# programmer_328.net
KiCad netlist of a schematic drawn in EAGLE
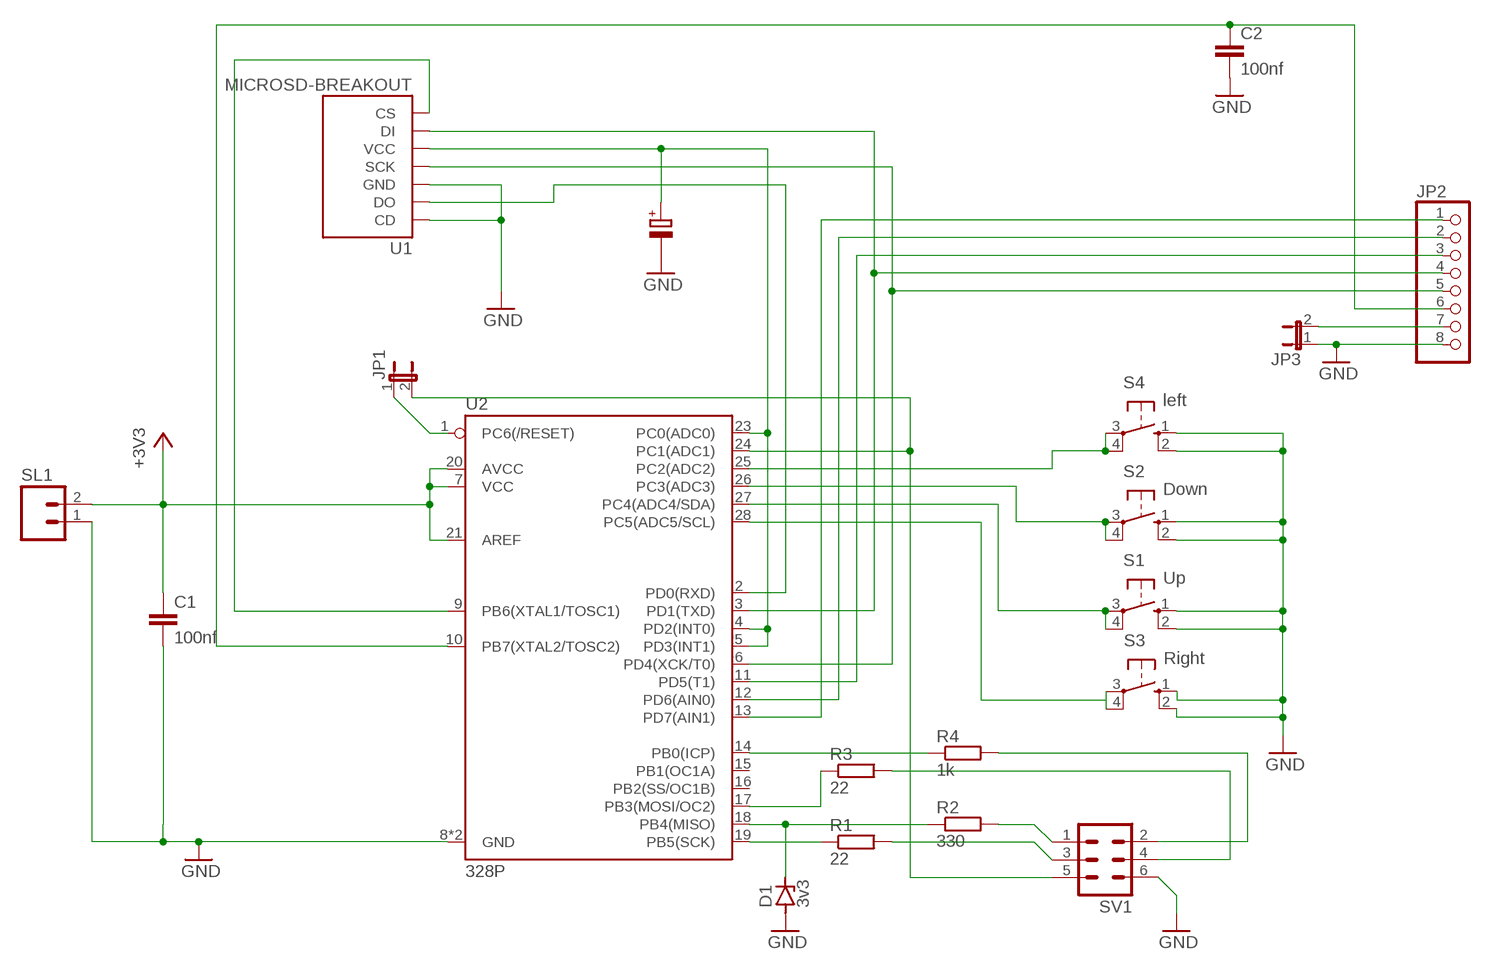
[diagram p0: schematic, sheet 1]

(export (version "E")
  (design (tool "Eeschema 10.0.6"))
  (components
    (comp (ref "C1")
      (value "100nf")
      (footprint "eagle-import:C2.5-2")
      (libsource (lib "eagle-import") (part "C2.5/2"))
    )
    (comp (ref "C2")
      (value "100nf")
      (footprint "eagle-import:C2.5-2")
      (libsource (lib "eagle-import") (part "C2.5/2"))
    )
    (comp (ref "D1")
      (value "3v3")
      (footprint "eagle-import:DO41Z10")
      (libsource (lib "eagle-import") (part "ZENER-DIODEDO41Z10"))
    )
    (comp (ref "JP1")
      (value "JP1E")
      (footprint "eagle-import:JP1")
      (libsource (lib "eagle-import") (part "JP1E"))
    )
    (comp (ref "JP2")
      (value "PINHD-1X8")
      (footprint "eagle-import:1X08")
      (libsource (lib "eagle-import") (part "PINHD-1X8"))
    )
    (comp (ref "JP3")
      (value "JP1E")
      (footprint "eagle-import:JP1")
      (libsource (lib "eagle-import") (part "JP1E"))
    )
    (comp (ref "R1")
      (value "22")
      (footprint "eagle-import:0207_12")
      (libsource (lib "eagle-import") (part "R-EU_0207/12"))
    )
    (comp (ref "R2")
      (value "330")
      (footprint "eagle-import:0207_12")
      (libsource (lib "eagle-import") (part "R-EU_0207/12"))
    )
    (comp (ref "R3")
      (value "22")
      (footprint "eagle-import:0207_12")
      (libsource (lib "eagle-import") (part "R-EU_0207/12"))
    )
    (comp (ref "R4")
      (value "1k")
      (footprint "eagle-import:0207_12")
      (libsource (lib "eagle-import") (part "R-EU_0207/12"))
    )
    (comp (ref "S1")
      (value "Up")
      (footprint "eagle-import:B3F-10XX")
      (fields (field (name "MPN") "B3F-1000"))
      (libsource (lib "eagle-import") (part "10-XX"))
    )
    (comp (ref "S2")
      (value "Down")
      (footprint "eagle-import:B3F-10XX")
      (fields (field (name "MPN") "B3F-1000"))
      (libsource (lib "eagle-import") (part "10-XX"))
    )
    (comp (ref "S3")
      (value "Right")
      (footprint "eagle-import:B3F-10XX")
      (fields (field (name "MPN") "B3F-1000"))
      (libsource (lib "eagle-import") (part "10-XX"))
    )
    (comp (ref "S4")
      (value "left")
      (footprint "eagle-import:B3F-10XX")
      (fields (field (name "MPN") "B3F-1000"))
      (libsource (lib "eagle-import") (part "10-XX"))
    )
    (comp (ref "SL1")
      (value "M02")
      (footprint "eagle-import:02P")
      (libsource (lib "eagle-import") (part "M02"))
    )
    (comp (ref "SV1")
      (value "MA03-2")
      (footprint "eagle-import:MA03-2")
      (libsource (lib "eagle-import") (part "MA03-2"))
    )
    (comp (ref "U1")
      (value "MICROSD-BREAKOUT")
      (footprint "eagle-import:MICROSD-BREAKOUT")
      (libsource (lib "eagle-import") (part "MICROSD-BREAKOUT"))
    )
    (comp (ref "U2")
      (value "328P")
      (footprint "eagle-import:DIP28")
      (libsource (lib "eagle-import") (part "ATMEGA328P_PDIP"))
    )
  )
  (nets
    (net (code "1") (name "+3V3") (class "Default")
      (node (ref "C1") (pin "1") (pinfunction "1_1") (pintype "passive"))
      (node (ref "SL1") (pin "2") (pinfunction "2_2") (pintype "passive"))
      (node (ref "U2") (pin "20") (pinfunction "AVCC_20") (pintype "bidirectional"))
      (node (ref "U2") (pin "21") (pinfunction "AREF_21") (pintype "bidirectional"))
      (node (ref "U2") (pin "7") (pinfunction "VCC_7") (pintype "bidirectional"))
    )
    (net (code "2") (name "GND") (class "Default")
      (node (ref "C1") (pin "2") (pinfunction "2_2") (pintype "passive"))
      (node (ref "C2") (pin "2") (pinfunction "2_2") (pintype "passive"))
      (node (ref "D1") (pin "A") (pinfunction "A_A") (pintype "passive"))
      (node (ref "JP2") (pin "8") (pinfunction "8_8") (pintype "passive"))
      (node (ref "JP3") (pin "1") (pinfunction "1_1") (pintype "passive"))
      (node (ref "S1") (pin "1") (pinfunction "S_1") (pintype "passive"))
      (node (ref "S1") (pin "2") (pinfunction "S1_2") (pintype "passive"))
      (node (ref "S2") (pin "1") (pinfunction "S_1") (pintype "passive"))
      (node (ref "S2") (pin "2") (pinfunction "S1_2") (pintype "passive"))
      (node (ref "S3") (pin "1") (pinfunction "S_1") (pintype "passive"))
      (node (ref "S3") (pin "2") (pinfunction "S1_2") (pintype "passive"))
      (node (ref "S4") (pin "1") (pinfunction "S_1") (pintype "passive"))
      (node (ref "S4") (pin "2") (pinfunction "S1_2") (pintype "passive"))
      (node (ref "SL1") (pin "1") (pinfunction "1_1") (pintype "passive"))
      (node (ref "SV1") (pin "6") (pinfunction "6_6") (pintype "passive"))
      (node (ref "U1") (pin "CD") (pinfunction "CD_CD") (pintype "bidirectional"))
      (node (ref "U1") (pin "GND") (pinfunction "GND_GND") (pintype "power_in"))
      (node (ref "U2") (pin "22") (pinfunction "GND_22") (pintype "bidirectional"))
      (node (ref "U2") (pin "8") (pinfunction "GND_8") (pintype "bidirectional"))
    )
    (net (code "3") (name "Net-(JP2-Pad7)") (class "Default")
      (node (ref "JP2") (pin "7") (pinfunction "7_7") (pintype "passive"))
      (node (ref "JP3") (pin "2") (pinfunction "2_2") (pintype "passive"))
    )
    (net (code "4") (name "Net-(R1-Pad2)") (class "Default")
      (node (ref "R1") (pin "2") (pinfunction "2_2") (pintype "passive"))
      (node (ref "SV1") (pin "3") (pinfunction "3_3") (pintype "passive"))
    )
    (net (code "5") (name "Net-(R2-Pad2)") (class "Default")
      (node (ref "R2") (pin "2") (pinfunction "2_2") (pintype "passive"))
      (node (ref "SV1") (pin "1") (pinfunction "1_1") (pintype "passive"))
    )
    (net (code "6") (name "Net-(R3-Pad2)") (class "Default")
      (node (ref "R3") (pin "2") (pinfunction "2_2") (pintype "passive"))
      (node (ref "SV1") (pin "4") (pinfunction "4_4") (pintype "passive"))
    )
    (net (code "7") (name "Net-(R4-Pad2)") (class "Default")
      (node (ref "R4") (pin "2") (pinfunction "2_2") (pintype "passive"))
      (node (ref "SV1") (pin "2") (pinfunction "2_2") (pintype "passive"))
    )
    (net (code "8") (name "Net-(S1-P)") (class "Default")
      (node (ref "S1") (pin "3") (pinfunction "P_3") (pintype "passive"))
      (node (ref "S1") (pin "4") (pinfunction "P1_4") (pintype "passive"))
      (node (ref "U2") (pin "27") (pinfunction "PC4(ADC4/SDA)_27") (pintype "bidirectional"))
    )
    (net (code "9") (name "Net-(S2-P)") (class "Default")
      (node (ref "S2") (pin "3") (pinfunction "P_3") (pintype "passive"))
      (node (ref "S2") (pin "4") (pinfunction "P1_4") (pintype "passive"))
      (node (ref "U2") (pin "26") (pinfunction "PC3(ADC3)_26") (pintype "bidirectional"))
    )
    (net (code "10") (name "Net-(S3-P)") (class "Default")
      (node (ref "S3") (pin "3") (pinfunction "P_3") (pintype "passive"))
      (node (ref "S3") (pin "4") (pinfunction "P1_4") (pintype "passive"))
    )
    (net (code "11") (name "Net-(S4-P)") (class "Default")
      (node (ref "S4") (pin "3") (pinfunction "P_3") (pintype "passive"))
      (node (ref "S4") (pin "4") (pinfunction "P1_4") (pintype "passive"))
      (node (ref "U2") (pin "25") (pinfunction "PC2(ADC2)_25") (pintype "bidirectional"))
    )
    (net (code "12") (name "Net-(U2-PB0(ICP))") (class "Default")
      (node (ref "R4") (pin "1") (pinfunction "1_1") (pintype "passive"))
      (node (ref "U2") (pin "14") (pinfunction "PB0(ICP)_14") (pintype "bidirectional"))
    )
    (net (code "13") (name "Net-(U2-PB3(MOSI{slash}OC2))") (class "Default")
      (node (ref "R3") (pin "1") (pinfunction "1_1") (pintype "passive"))
      (node (ref "U2") (pin "17") (pinfunction "PB3(MOSI/OC2)_17") (pintype "bidirectional"))
    )
    (net (code "14") (name "Net-(U2-PB4(MISO))") (class "Default")
      (node (ref "D1") (pin "C") (pinfunction "C_C") (pintype "passive"))
      (node (ref "R2") (pin "1") (pinfunction "1_1") (pintype "passive"))
      (node (ref "U2") (pin "18") (pinfunction "PB4(MISO)_18") (pintype "bidirectional"))
    )
    (net (code "15") (name "Net-(U2-PB5(SCK))") (class "Default")
      (node (ref "R1") (pin "1") (pinfunction "1_1") (pintype "passive"))
      (node (ref "U2") (pin "19") (pinfunction "PB5(SCK)_19") (pintype "bidirectional"))
    )
    (net (code "16") (name "Net-(U2-PB6(XTAL1{slash}TOSC1))") (class "Default")
      (node (ref "U1") (pin "CS") (pinfunction "CS_CS") (pintype "bidirectional"))
      (node (ref "U2") (pin "9") (pinfunction "PB6(XTAL1/TOSC1)_9") (pintype "bidirectional"))
    )
    (net (code "17") (name "Net-(U2-PB7(XTAL2{slash}TOSC2))") (class "Default")
      (node (ref "C2") (pin "1") (pinfunction "1_1") (pintype "passive"))
      (node (ref "JP2") (pin "6") (pinfunction "6_6") (pintype "passive"))
      (node (ref "U2") (pin "10") (pinfunction "PB7(XTAL2/TOSC2)_10") (pintype "bidirectional"))
    )
    (net (code "18") (name "Net-(U2-PC0(ADC0))") (class "Default")
      (node (ref "U1") (pin "VCC") (pinfunction "VCC_VCC") (pintype "bidirectional"))
      (node (ref "U2") (pin "23") (pinfunction "PC0(ADC0)_23") (pintype "bidirectional"))
      (node (ref "U2") (pin "4") (pinfunction "PD2(INT0)_4") (pintype "bidirectional"))
      (node (ref "U2") (pin "5") (pinfunction "PD3(INT1)_5") (pintype "bidirectional"))
    )
    (net (code "19") (name "Net-(U2-PC1(ADC1))") (class "Default")
      (node (ref "JP1") (pin "2") (pinfunction "2_2") (pintype "passive"))
      (node (ref "SV1") (pin "5") (pinfunction "5_5") (pintype "passive"))
      (node (ref "U2") (pin "24") (pinfunction "PC1(ADC1)_24") (pintype "bidirectional"))
    )
    (net (code "20") (name "Net-(U2-PC6({slash}RESET))") (class "Default")
      (node (ref "JP1") (pin "1") (pinfunction "1_1") (pintype "passive"))
      (node (ref "U2") (pin "1") (pinfunction "PC6(/RESET)_1") (pintype "bidirectional"))
    )
    (net (code "21") (name "Net-(U2-PD0(RXD))") (class "Default")
      (node (ref "U1") (pin "DO") (pinfunction "DO_DO") (pintype "bidirectional"))
      (node (ref "U2") (pin "2") (pinfunction "PD0(RXD)_2") (pintype "bidirectional"))
    )
    (net (code "22") (name "Net-(U2-PD1(TXD))") (class "Default")
      (node (ref "JP2") (pin "4") (pinfunction "4_4") (pintype "passive"))
      (node (ref "U1") (pin "DI") (pinfunction "DI_DI") (pintype "bidirectional"))
      (node (ref "U2") (pin "3") (pinfunction "PD1(TXD)_3") (pintype "bidirectional"))
    )
    (net (code "23") (name "Net-(U2-PD4(XCK{slash}T0))") (class "Default")
      (node (ref "JP2") (pin "5") (pinfunction "5_5") (pintype "passive"))
      (node (ref "U1") (pin "SCK") (pinfunction "SCK_SCK") (pintype "bidirectional"))
      (node (ref "U2") (pin "6") (pinfunction "PD4(XCK/T0)_6") (pintype "bidirectional"))
    )
    (net (code "24") (name "Net-(U2-PD5(T1))") (class "Default")
      (node (ref "JP2") (pin "3") (pinfunction "3_3") (pintype "passive"))
      (node (ref "U2") (pin "11") (pinfunction "PD5(T1)_11") (pintype "bidirectional"))
    )
    (net (code "25") (name "Net-(U2-PD6(AIN0))") (class "Default")
      (node (ref "JP2") (pin "2") (pinfunction "2_2") (pintype "passive"))
      (node (ref "U2") (pin "12") (pinfunction "PD6(AIN0)_12") (pintype "bidirectional"))
    )
    (net (code "26") (name "Net-(U2-PD7(AIN1))") (class "Default")
      (node (ref "JP2") (pin "1") (pinfunction "1_1") (pintype "passive"))
      (node (ref "U2") (pin "13") (pinfunction "PD7(AIN1)_13") (pintype "bidirectional"))
    )
    (net (code "27") (name "unconnected-(U2-PB1(OC1A)-Pad15)") (class "Default")
      (node (ref "U2") (pin "15") (pinfunction "PB1(OC1A)_15") (pintype "bidirectional"))
    )
    (net (code "28") (name "unconnected-(U2-PB2(SS{slash}OC1B)-Pad16)") (class "Default")
      (node (ref "U2") (pin "16") (pinfunction "PB2(SS/OC1B)_16") (pintype "bidirectional"))
    )
    (net (code "29") (name "unconnected-(U2-PC5(ADC5{slash}SCL)-Pad28)") (class "Default")
      (node (ref "U2") (pin "28") (pinfunction "PC5(ADC5/SCL)_28") (pintype "bidirectional"))
    )
  )
)
